# TSAL_mainboard.net
KiCad netlist of a schematic drawn in EAGLE
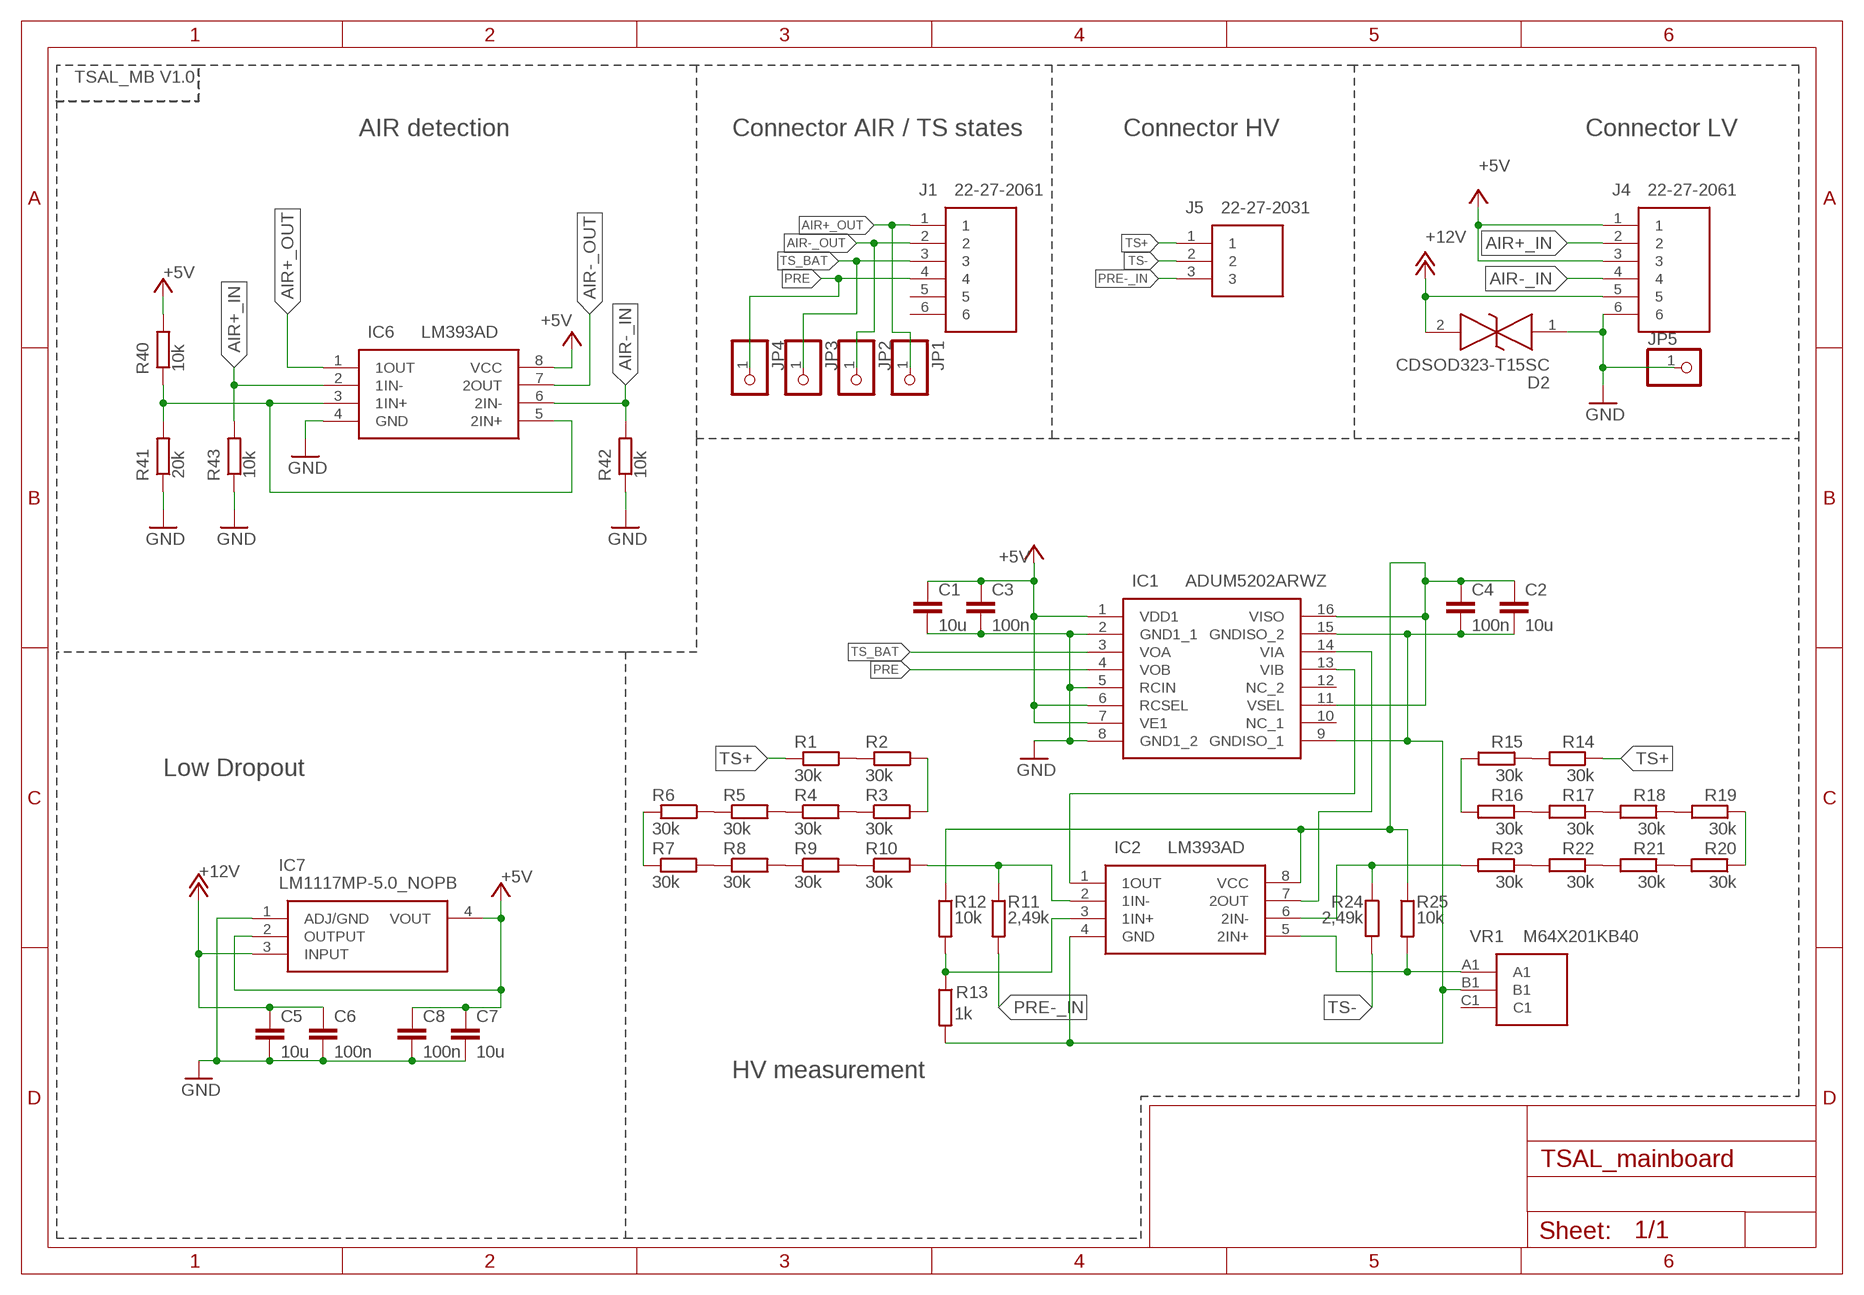
[diagram p0: schematic, sheet 1]

(export (version "E")
  (design (tool "Eeschema 10.0.6"))
  (components
    (comp (ref "C1")
      (value "10u")
      (footprint "eagle-import:C1206")
      (libsource (lib "eagle-import") (part "C-EUC1206"))
    )
    (comp (ref "C2")
      (value "10u")
      (footprint "eagle-import:C1206")
      (libsource (lib "eagle-import") (part "C-EUC1206"))
    )
    (comp (ref "C3")
      (value "100n")
      (footprint "eagle-import:C0603")
      (libsource (lib "eagle-import") (part "C-EUC0603"))
    )
    (comp (ref "C4")
      (value "100n")
      (footprint "eagle-import:C0603")
      (libsource (lib "eagle-import") (part "C-EUC0603"))
    )
    (comp (ref "C5")
      (value "10u")
      (footprint "eagle-import:C1206")
      (libsource (lib "eagle-import") (part "C-EUC1206"))
    )
    (comp (ref "C6")
      (value "100n")
      (footprint "eagle-import:C0603")
      (libsource (lib "eagle-import") (part "C-EUC0603"))
    )
    (comp (ref "C7")
      (value "10u")
      (footprint "eagle-import:C1206")
      (libsource (lib "eagle-import") (part "C-EUC1206"))
    )
    (comp (ref "C8")
      (value "100n")
      (footprint "eagle-import:C0603")
      (libsource (lib "eagle-import") (part "C-EUC0603"))
    )
    (comp (ref "D2")
      (value "CDSOD323-T15SC")
      (footprint "eagle-import:SOD-323")
      (fields (field (name "RS_PART_NUMBER") "7734570"))
      (libsource (lib "eagle-import") (part "CDSOD323-T15SC"))
    )
    (comp (ref "IC1")
      (value "ADUM5202ARWZ")
      (footprint "eagle-import:SOIC127P1032X265-16N")
      (fields (field (name "MOUSER_PART_NUMBER") "584-ADUM5202ARWZ"))
      (libsource (lib "eagle-import") (part "ADUM5202ARWZ"))
    )
    (comp (ref "IC2")
      (value "LM393AD")
      (footprint "eagle-import:SOIC127P600X175-8N")
      (fields (field (name "RS_PART_NUMBER") "5171905P"))
      (libsource (lib "eagle-import") (part "LM393AD"))
    )
    (comp (ref "IC6")
      (value "LM393AD")
      (footprint "eagle-import:SOIC127P600X175-8N")
      (fields (field (name "RS_PART_NUMBER") "5171905P"))
      (libsource (lib "eagle-import") (part "LM393AD"))
    )
    (comp (ref "IC7")
      (value "LM1117MP-5.0_NOPB")
      (footprint "eagle-import:SOT230P700X180-4N")
      (fields
        (field (name "ARROW_PART_NUMBER") "LM1117MP-5.0/NOPB")
        (field (name "MOUSER_PART_NUMBER") "926-LM1117MP-5.0NOPB")
      )
      (libsource (lib "eagle-import") (part "LM1117MP-5.0_NOPB"))
    )
    (comp (ref "J1")
      (value "22-27-2061")
      (footprint "eagle-import:HDRV6W64P0X254_1X6_1524X580X11")
      (fields (field (name "RS_PART_NUMBER") "4838506P"))
      (libsource (lib "eagle-import") (part "22-27-2061"))
    )
    (comp (ref "J4")
      (value "22-27-2061")
      (footprint "eagle-import:HDRV6W64P0X254_1X6_1524X580X11")
      (fields (field (name "RS_PART_NUMBER") "4838506P"))
      (libsource (lib "eagle-import") (part "22-27-2061"))
    )
    (comp (ref "J5")
      (value "22-27-2031")
      (footprint "eagle-import:SHDR3W64P0X254_1X3_762X580X111")
      (fields (field (name "RS_PART_NUMBER") "4838477P"))
      (libsource (lib "eagle-import") (part "22-27-2031"))
    )
    (comp (ref "JP1")
      (value "PINHD-1X1")
      (footprint "eagle-import:1X01")
      (libsource (lib "eagle-import") (part "PINHD-1X1"))
    )
    (comp (ref "JP2")
      (value "PINHD-1X1")
      (footprint "eagle-import:1X01")
      (libsource (lib "eagle-import") (part "PINHD-1X1"))
    )
    (comp (ref "JP3")
      (value "PINHD-1X1")
      (footprint "eagle-import:1X01")
      (libsource (lib "eagle-import") (part "PINHD-1X1"))
    )
    (comp (ref "JP4")
      (value "PINHD-1X1")
      (footprint "eagle-import:1X01")
      (libsource (lib "eagle-import") (part "PINHD-1X1"))
    )
    (comp (ref "JP5")
      (value "PINHD-1X1")
      (footprint "eagle-import:1X01")
      (libsource (lib "eagle-import") (part "PINHD-1X1"))
    )
    (comp (ref "R1")
      (value "30k")
      (footprint "eagle-import:R1206")
      (libsource (lib "eagle-import") (part "R-EU_R1206"))
    )
    (comp (ref "R2")
      (value "30k")
      (footprint "eagle-import:R1206")
      (libsource (lib "eagle-import") (part "R-EU_R1206"))
    )
    (comp (ref "R3")
      (value "30k")
      (footprint "eagle-import:R1206")
      (libsource (lib "eagle-import") (part "R-EU_R1206"))
    )
    (comp (ref "R4")
      (value "30k")
      (footprint "eagle-import:R1206")
      (libsource (lib "eagle-import") (part "R-EU_R1206"))
    )
    (comp (ref "R5")
      (value "30k")
      (footprint "eagle-import:R1206")
      (libsource (lib "eagle-import") (part "R-EU_R1206"))
    )
    (comp (ref "R6")
      (value "30k")
      (footprint "eagle-import:R1206")
      (libsource (lib "eagle-import") (part "R-EU_R1206"))
    )
    (comp (ref "R7")
      (value "30k")
      (footprint "eagle-import:R1206")
      (libsource (lib "eagle-import") (part "R-EU_R1206"))
    )
    (comp (ref "R8")
      (value "30k")
      (footprint "eagle-import:R1206")
      (libsource (lib "eagle-import") (part "R-EU_R1206"))
    )
    (comp (ref "R9")
      (value "30k")
      (footprint "eagle-import:R1206")
      (libsource (lib "eagle-import") (part "R-EU_R1206"))
    )
    (comp (ref "R10")
      (value "30k")
      (footprint "eagle-import:R1206")
      (libsource (lib "eagle-import") (part "R-EU_R1206"))
    )
    (comp (ref "R11")
      (value "2,49k")
      (footprint "eagle-import:R0603")
      (libsource (lib "eagle-import") (part "R-EU_R0603"))
    )
    (comp (ref "R12")
      (value "10k")
      (footprint "eagle-import:R0603")
      (libsource (lib "eagle-import") (part "R-EU_R0603"))
    )
    (comp (ref "R13")
      (value "1k")
      (footprint "eagle-import:R1206")
      (libsource (lib "eagle-import") (part "R-EU_R1206"))
    )
    (comp (ref "R14")
      (value "30k")
      (footprint "eagle-import:R1206")
      (libsource (lib "eagle-import") (part "R-EU_R1206"))
    )
    (comp (ref "R15")
      (value "30k")
      (footprint "eagle-import:R1206")
      (libsource (lib "eagle-import") (part "R-EU_R1206"))
    )
    (comp (ref "R16")
      (value "30k")
      (footprint "eagle-import:R1206")
      (libsource (lib "eagle-import") (part "R-EU_R1206"))
    )
    (comp (ref "R17")
      (value "30k")
      (footprint "eagle-import:R1206")
      (libsource (lib "eagle-import") (part "R-EU_R1206"))
    )
    (comp (ref "R18")
      (value "30k")
      (footprint "eagle-import:R1206")
      (libsource (lib "eagle-import") (part "R-EU_R1206"))
    )
    (comp (ref "R19")
      (value "30k")
      (footprint "eagle-import:R1206")
      (libsource (lib "eagle-import") (part "R-EU_R1206"))
    )
    (comp (ref "R20")
      (value "30k")
      (footprint "eagle-import:R1206")
      (libsource (lib "eagle-import") (part "R-EU_R1206"))
    )
    (comp (ref "R21")
      (value "30k")
      (footprint "eagle-import:R1206")
      (libsource (lib "eagle-import") (part "R-EU_R1206"))
    )
    (comp (ref "R22")
      (value "30k")
      (footprint "eagle-import:R1206")
      (libsource (lib "eagle-import") (part "R-EU_R1206"))
    )
    (comp (ref "R23")
      (value "30k")
      (footprint "eagle-import:R1206")
      (libsource (lib "eagle-import") (part "R-EU_R1206"))
    )
    (comp (ref "R24")
      (value "2,49k")
      (footprint "eagle-import:R0603")
      (libsource (lib "eagle-import") (part "R-EU_R0603"))
    )
    (comp (ref "R25")
      (value "10k")
      (footprint "eagle-import:R0603")
      (libsource (lib "eagle-import") (part "R-EU_R0603"))
    )
    (comp (ref "R40")
      (value "10k")
      (footprint "eagle-import:R0603")
      (libsource (lib "eagle-import") (part "R-EU_R0603"))
    )
    (comp (ref "R41")
      (value "20k")
      (footprint "eagle-import:R0603")
      (libsource (lib "eagle-import") (part "R-EU_R0603"))
    )
    (comp (ref "R42")
      (value "10k")
      (footprint "eagle-import:R0603")
      (libsource (lib "eagle-import") (part "R-EU_R0603"))
    )
    (comp (ref "R43")
      (value "10k")
      (footprint "eagle-import:R0603")
      (libsource (lib "eagle-import") (part "R-EU_R0603"))
    )
    (comp (ref "VR1")
      (value "M64X201KB40")
      (footprint "eagle-import:M64X201KB40")
      (fields (field (name "MOUSER_PART_NUMBER") "594-64X201"))
      (libsource (lib "eagle-import") (part "M64X201KB40"))
    )
  )
  (nets
    (net (code "1") (name "+5V") (class "Default")
      (node (ref "C1") (pin "1") (pinfunction "1_1") (pintype "passive"))
      (node (ref "C3") (pin "1") (pinfunction "1_1") (pintype "passive"))
      (node (ref "C7") (pin "1") (pinfunction "1_1") (pintype "passive"))
      (node (ref "C8") (pin "1") (pinfunction "1_1") (pintype "passive"))
      (node (ref "IC1") (pin "1") (pinfunction "VDD1_1") (pintype "power_in"))
      (node (ref "IC1") (pin "6") (pinfunction "RCSEL_6") (pintype "input"))
      (node (ref "IC1") (pin "7") (pinfunction "VE1_7") (pintype "bidirectional"))
      (node (ref "IC6") (pin "8") (pinfunction "VCC_8") (pintype "bidirectional"))
      (node (ref "IC7") (pin "2") (pinfunction "OUTPUT_2") (pintype "bidirectional"))
      (node (ref "IC7") (pin "4") (pinfunction "VOUT_4") (pintype "bidirectional"))
      (node (ref "J4") (pin "1") (pinfunction "1_1") (pintype "bidirectional"))
      (node (ref "J4") (pin "3") (pinfunction "3_3") (pintype "bidirectional"))
      (node (ref "R40") (pin "2") (pinfunction "2_2") (pintype "passive"))
    )
    (net (code "2") (name "+12V") (class "Default")
      (node (ref "C5") (pin "1") (pinfunction "1_1") (pintype "passive"))
      (node (ref "C6") (pin "1") (pinfunction "1_1") (pintype "passive"))
      (node (ref "D2") (pin "2") (pinfunction "2_2") (pintype "bidirectional"))
      (node (ref "IC7") (pin "3") (pinfunction "INPUT_3") (pintype "bidirectional"))
      (node (ref "J4") (pin "5") (pinfunction "5_5") (pintype "bidirectional"))
    )
    (net (code "3") (name "AIR+_IN") (class "Default")
      (node (ref "IC6") (pin "2") (pinfunction "1IN-_2") (pintype "bidirectional"))
      (node (ref "J4") (pin "2") (pinfunction "2_2") (pintype "bidirectional"))
      (node (ref "R43") (pin "2") (pinfunction "2_2") (pintype "passive"))
    )
    (net (code "4") (name "AIR+_OUT") (class "Default")
      (node (ref "IC6") (pin "1") (pinfunction "1OUT_1") (pintype "bidirectional"))
      (node (ref "J1") (pin "1") (pinfunction "1_1") (pintype "bidirectional"))
      (node (ref "JP1") (pin "1") (pinfunction "1_1") (pintype "passive"))
    )
    (net (code "5") (name "AIR-_IN") (class "Default")
      (node (ref "IC6") (pin "6") (pinfunction "2IN-_6") (pintype "bidirectional"))
      (node (ref "J4") (pin "4") (pinfunction "4_4") (pintype "bidirectional"))
      (node (ref "R42") (pin "2") (pinfunction "2_2") (pintype "passive"))
    )
    (net (code "6") (name "AIR-_OUT") (class "Default")
      (node (ref "IC6") (pin "7") (pinfunction "2OUT_7") (pintype "bidirectional"))
      (node (ref "J1") (pin "2") (pinfunction "2_2") (pintype "bidirectional"))
      (node (ref "JP2") (pin "1") (pinfunction "1_1") (pintype "passive"))
    )
    (net (code "7") (name "GND") (class "Default")
      (node (ref "C1") (pin "2") (pinfunction "2_2") (pintype "passive"))
      (node (ref "C3") (pin "2") (pinfunction "2_2") (pintype "passive"))
      (node (ref "C5") (pin "2") (pinfunction "2_2") (pintype "passive"))
      (node (ref "C6") (pin "2") (pinfunction "2_2") (pintype "passive"))
      (node (ref "C7") (pin "2") (pinfunction "2_2") (pintype "passive"))
      (node (ref "C8") (pin "2") (pinfunction "2_2") (pintype "passive"))
      (node (ref "D2") (pin "1") (pinfunction "1_1") (pintype "bidirectional"))
      (node (ref "IC1") (pin "2") (pinfunction "GND1_1_2") (pintype "power_in"))
      (node (ref "IC1") (pin "5") (pinfunction "RCIN_5") (pintype "input"))
      (node (ref "IC1") (pin "8") (pinfunction "GND1_2_8") (pintype "power_in"))
      (node (ref "IC6") (pin "4") (pinfunction "GND_4") (pintype "bidirectional"))
      (node (ref "IC7") (pin "1") (pinfunction "ADJ/GND_1") (pintype "bidirectional"))
      (node (ref "J4") (pin "6") (pinfunction "6_6") (pintype "bidirectional"))
      (node (ref "JP5") (pin "1") (pinfunction "1_1") (pintype "passive"))
      (node (ref "R41") (pin "1") (pinfunction "1_1") (pintype "passive"))
      (node (ref "R42") (pin "1") (pinfunction "1_1") (pintype "passive"))
      (node (ref "R43") (pin "1") (pinfunction "1_1") (pintype "passive"))
    )
    (net (code "8") (name "Net-(IC1-GNDISO_1)") (class "Default")
      (node (ref "C2") (pin "2") (pinfunction "2_2") (pintype "passive"))
      (node (ref "C4") (pin "2") (pinfunction "2_2") (pintype "passive"))
      (node (ref "IC1") (pin "15") (pinfunction "GNDISO_2_15") (pintype "power_in"))
      (node (ref "IC1") (pin "9") (pinfunction "GNDISO_1_9") (pintype "power_in"))
      (node (ref "IC2") (pin "4") (pinfunction "GND_4") (pintype "bidirectional"))
      (node (ref "R13") (pin "2") (pinfunction "2_2") (pintype "passive"))
      (node (ref "VR1") (pin "B1") (pinfunction "B1_B1") (pintype "bidirectional"))
    )
    (net (code "9") (name "Net-(IC1-VIA)") (class "Default")
      (node (ref "IC1") (pin "14") (pinfunction "VIA_14") (pintype "bidirectional"))
      (node (ref "IC2") (pin "7") (pinfunction "2OUT_7") (pintype "bidirectional"))
    )
    (net (code "10") (name "Net-(IC1-VIB)") (class "Default")
      (node (ref "IC1") (pin "13") (pinfunction "VIB_13") (pintype "bidirectional"))
      (node (ref "IC2") (pin "1") (pinfunction "1OUT_1") (pintype "bidirectional"))
    )
    (net (code "11") (name "Net-(IC1-VISO)") (class "Default")
      (node (ref "C2") (pin "1") (pinfunction "1_1") (pintype "passive"))
      (node (ref "C4") (pin "1") (pinfunction "1_1") (pintype "passive"))
      (node (ref "IC1") (pin "11") (pinfunction "VSEL_11") (pintype "bidirectional"))
      (node (ref "IC1") (pin "16") (pinfunction "VISO_16") (pintype "bidirectional"))
      (node (ref "IC2") (pin "8") (pinfunction "VCC_8") (pintype "bidirectional"))
      (node (ref "R12") (pin "1") (pinfunction "1_1") (pintype "passive"))
      (node (ref "R25") (pin "1") (pinfunction "1_1") (pintype "passive"))
    )
    (net (code "12") (name "Net-(IC2-1IN+)") (class "Default")
      (node (ref "IC2") (pin "3") (pinfunction "1IN+_3") (pintype "bidirectional"))
      (node (ref "R12") (pin "2") (pinfunction "2_2") (pintype "passive"))
      (node (ref "R13") (pin "1") (pinfunction "1_1") (pintype "passive"))
    )
    (net (code "13") (name "Net-(IC2-1IN-)") (class "Default")
      (node (ref "IC2") (pin "2") (pinfunction "1IN-_2") (pintype "bidirectional"))
      (node (ref "R10") (pin "2") (pinfunction "2_2") (pintype "passive"))
      (node (ref "R11") (pin "1") (pinfunction "1_1") (pintype "passive"))
    )
    (net (code "14") (name "Net-(IC2-2IN+)") (class "Default")
      (node (ref "IC2") (pin "5") (pinfunction "2IN+_5") (pintype "bidirectional"))
      (node (ref "R25") (pin "2") (pinfunction "2_2") (pintype "passive"))
      (node (ref "VR1") (pin "A1") (pinfunction "A1_A1") (pintype "bidirectional"))
    )
    (net (code "15") (name "Net-(IC2-2IN-)") (class "Default")
      (node (ref "IC2") (pin "6") (pinfunction "2IN-_6") (pintype "bidirectional"))
      (node (ref "R23") (pin "2") (pinfunction "2_2") (pintype "passive"))
      (node (ref "R24") (pin "1") (pinfunction "1_1") (pintype "passive"))
    )
    (net (code "16") (name "Net-(IC6-1IN+)") (class "Default")
      (node (ref "IC6") (pin "3") (pinfunction "1IN+_3") (pintype "bidirectional"))
      (node (ref "IC6") (pin "5") (pinfunction "2IN+_5") (pintype "bidirectional"))
      (node (ref "R40") (pin "1") (pinfunction "1_1") (pintype "passive"))
      (node (ref "R41") (pin "2") (pinfunction "2_2") (pintype "passive"))
    )
    (net (code "17") (name "Net-(R1-Pad1)") (class "Default")
      (node (ref "R1") (pin "1") (pinfunction "1_1") (pintype "passive"))
      (node (ref "R2") (pin "2") (pinfunction "2_2") (pintype "passive"))
    )
    (net (code "18") (name "Net-(R2-Pad1)") (class "Default")
      (node (ref "R2") (pin "1") (pinfunction "1_1") (pintype "passive"))
      (node (ref "R3") (pin "2") (pinfunction "2_2") (pintype "passive"))
    )
    (net (code "19") (name "Net-(R3-Pad1)") (class "Default")
      (node (ref "R3") (pin "1") (pinfunction "1_1") (pintype "passive"))
      (node (ref "R4") (pin "2") (pinfunction "2_2") (pintype "passive"))
    )
    (net (code "20") (name "Net-(R4-Pad1)") (class "Default")
      (node (ref "R4") (pin "1") (pinfunction "1_1") (pintype "passive"))
      (node (ref "R5") (pin "2") (pinfunction "2_2") (pintype "passive"))
    )
    (net (code "21") (name "Net-(R5-Pad1)") (class "Default")
      (node (ref "R5") (pin "1") (pinfunction "1_1") (pintype "passive"))
      (node (ref "R6") (pin "1") (pinfunction "1_1") (pintype "passive"))
    )
    (net (code "22") (name "Net-(R6-Pad2)") (class "Default")
      (node (ref "R6") (pin "2") (pinfunction "2_2") (pintype "passive"))
      (node (ref "R7") (pin "1") (pinfunction "1_1") (pintype "passive"))
    )
    (net (code "23") (name "Net-(R7-Pad2)") (class "Default")
      (node (ref "R7") (pin "2") (pinfunction "2_2") (pintype "passive"))
      (node (ref "R8") (pin "1") (pinfunction "1_1") (pintype "passive"))
    )
    (net (code "24") (name "Net-(R8-Pad2)") (class "Default")
      (node (ref "R8") (pin "2") (pinfunction "2_2") (pintype "passive"))
      (node (ref "R9") (pin "1") (pinfunction "1_1") (pintype "passive"))
    )
    (net (code "25") (name "Net-(R10-Pad1)") (class "Default")
      (node (ref "R10") (pin "1") (pinfunction "1_1") (pintype "passive"))
      (node (ref "R9") (pin "2") (pinfunction "2_2") (pintype "passive"))
    )
    (net (code "26") (name "Net-(R14-Pad1)") (class "Default")
      (node (ref "R14") (pin "1") (pinfunction "1_1") (pintype "passive"))
      (node (ref "R15") (pin "2") (pinfunction "2_2") (pintype "passive"))
    )
    (net (code "27") (name "Net-(R15-Pad1)") (class "Default")
      (node (ref "R15") (pin "1") (pinfunction "1_1") (pintype "passive"))
      (node (ref "R16") (pin "2") (pinfunction "2_2") (pintype "passive"))
    )
    (net (code "28") (name "Net-(R16-Pad1)") (class "Default")
      (node (ref "R16") (pin "1") (pinfunction "1_1") (pintype "passive"))
      (node (ref "R17") (pin "2") (pinfunction "2_2") (pintype "passive"))
    )
    (net (code "29") (name "Net-(R17-Pad1)") (class "Default")
      (node (ref "R17") (pin "1") (pinfunction "1_1") (pintype "passive"))
      (node (ref "R18") (pin "2") (pinfunction "2_2") (pintype "passive"))
    )
    (net (code "30") (name "Net-(R18-Pad1)") (class "Default")
      (node (ref "R18") (pin "1") (pinfunction "1_1") (pintype "passive"))
      (node (ref "R19") (pin "1") (pinfunction "1_1") (pintype "passive"))
    )
    (net (code "31") (name "Net-(R19-Pad2)") (class "Default")
      (node (ref "R19") (pin "2") (pinfunction "2_2") (pintype "passive"))
      (node (ref "R20") (pin "1") (pinfunction "1_1") (pintype "passive"))
    )
    (net (code "32") (name "Net-(R20-Pad2)") (class "Default")
      (node (ref "R20") (pin "2") (pinfunction "2_2") (pintype "passive"))
      (node (ref "R21") (pin "1") (pinfunction "1_1") (pintype "passive"))
    )
    (net (code "33") (name "Net-(R21-Pad2)") (class "Default")
      (node (ref "R21") (pin "2") (pinfunction "2_2") (pintype "passive"))
      (node (ref "R22") (pin "1") (pinfunction "1_1") (pintype "passive"))
    )
    (net (code "34") (name "Net-(R22-Pad2)") (class "Default")
      (node (ref "R22") (pin "2") (pinfunction "2_2") (pintype "passive"))
      (node (ref "R23") (pin "1") (pinfunction "1_1") (pintype "passive"))
    )
    (net (code "35") (name "PRE") (class "Default")
      (node (ref "IC1") (pin "4") (pinfunction "VOB_4") (pintype "bidirectional"))
      (node (ref "J1") (pin "4") (pinfunction "4_4") (pintype "bidirectional"))
      (node (ref "JP4") (pin "1") (pinfunction "1_1") (pintype "passive"))
    )
    (net (code "36") (name "PRE-_IN") (class "Default")
      (node (ref "J5") (pin "3") (pinfunction "3_3") (pintype "bidirectional"))
      (node (ref "R11") (pin "2") (pinfunction "2_2") (pintype "passive"))
    )
    (net (code "37") (name "TS+") (class "Default")
      (node (ref "J5") (pin "1") (pinfunction "1_1") (pintype "bidirectional"))
      (node (ref "R1") (pin "2") (pinfunction "2_2") (pintype "passive"))
      (node (ref "R14") (pin "2") (pinfunction "2_2") (pintype "passive"))
    )
    (net (code "38") (name "TS-") (class "Default")
      (node (ref "J5") (pin "2") (pinfunction "2_2") (pintype "bidirectional"))
      (node (ref "R24") (pin "2") (pinfunction "2_2") (pintype "passive"))
    )
    (net (code "39") (name "TS_BAT") (class "Default")
      (node (ref "IC1") (pin "3") (pinfunction "VOA_3") (pintype "bidirectional"))
      (node (ref "J1") (pin "3") (pinfunction "3_3") (pintype "bidirectional"))
      (node (ref "JP3") (pin "1") (pinfunction "1_1") (pintype "passive"))
    )
    (net (code "40") (name "unconnected-(IC1-NC_1-Pad10)") (class "Default")
      (node (ref "IC1") (pin "10") (pinfunction "NC_1_10") (pintype "bidirectional"))
    )
    (net (code "41") (name "unconnected-(IC1-NC_2-Pad12)") (class "Default")
      (node (ref "IC1") (pin "12") (pinfunction "NC_2_12") (pintype "bidirectional"))
    )
    (net (code "42") (name "unconnected-(J1-Pad5)") (class "Default")
      (node (ref "J1") (pin "5") (pinfunction "5_5") (pintype "bidirectional"))
    )
    (net (code "43") (name "unconnected-(J1-Pad6)") (class "Default")
      (node (ref "J1") (pin "6") (pinfunction "6_6") (pintype "bidirectional"))
    )
    (net (code "44") (name "unconnected-(VR1-PadC1)") (class "Default")
      (node (ref "VR1") (pin "C1") (pinfunction "C1_C1") (pintype "bidirectional"))
    )
  )
)
